# NIR_Schematic.net
KiCad netlist of a schematic drawn in EasyEDA
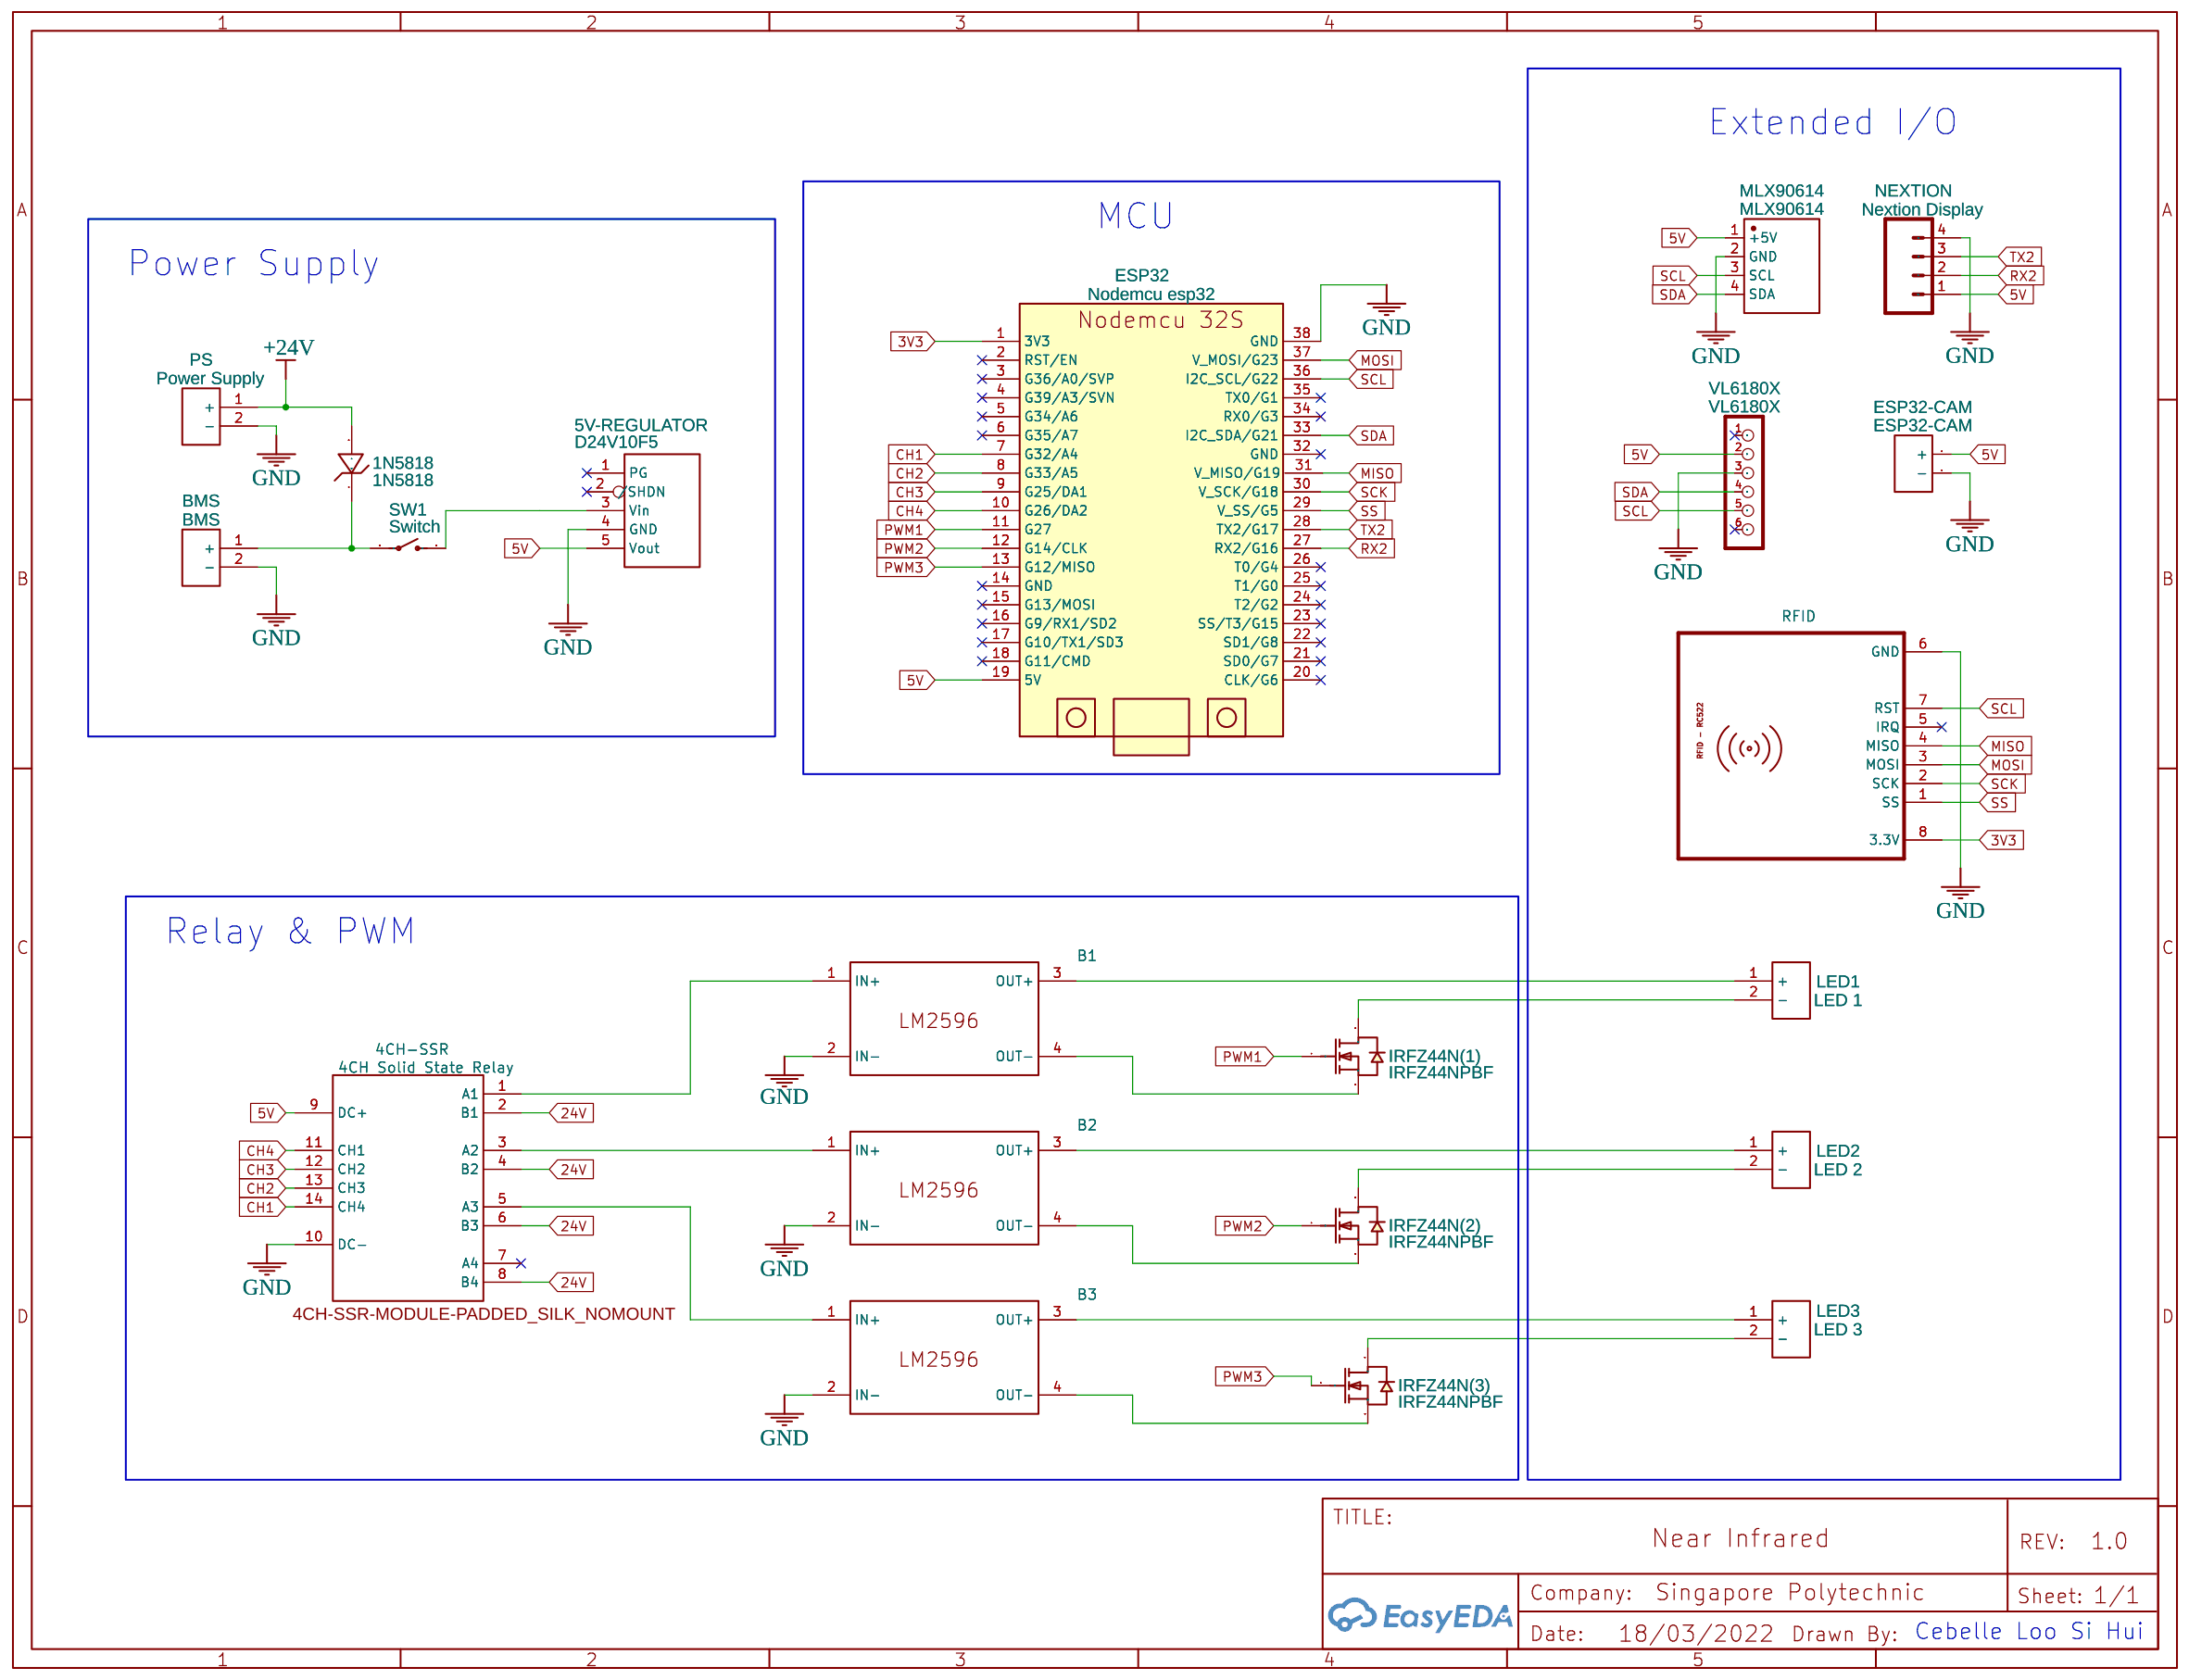
[diagram p0: schematic sheet]

(export (version "E")
  (design (tool "Eeschema 10.0.6"))
  (components
    (comp (ref "1N5818")
      (value "1N5818")
      (fields (field (name "BOM_Supplier Part") "C402217"))
      (libsource (lib "") (part "1N5818"))
    )
    (comp (ref "4CH-SSR") (value "4CH Solid State Relay") (libsource (lib "") (part "Unknown_210_-255")))
    (comp (ref "5V-REGULATOR") (value "D24V10F5") (libsource (lib "") (part "D24V10F5")))
    (comp (ref "B1") (value "NO") (libsource (lib "") (part "Unknown_495_-345")))
    (comp (ref "B2") (value "NO") (libsource (lib "") (part "Unknown_495_-255")))
    (comp (ref "B3") (value "NO") (libsource (lib "") (part "Unknown_495_-165")))
    (comp (ref "BMS")
      (value "BMS")
      (fields
        (field (name "BOM_Manufacturer Part") "WJ103-5.00-2P")
        (field (name "BOM_Supplier Part") "C8439")
      )
      (libsource (lib "") (part "WJ103-5.00-2P_1"))
    )
    (comp (ref "ESP32") (value "Nodemcu esp32") (libsource (lib "") (part "Nodemcu esp32")))
    (comp (ref "ESP32-CAM")
      (value "ESP32-CAM")
      (fields
        (field (name "BOM_Manufacturer Part") "2.54-1*2PFemale")
        (field (name "BOM_Supplier Part") "C49661")
      )
      (libsource (lib "") (part "Header-Female-2.54_1x2"))
    )
    (comp (ref "IRFZ44N(1)")
      (value "IRFZ44NPBF")
      (fields (field (name "BOM_Supplier Part") "C2586"))
      (libsource (lib "") (part "IRFZ44NPBF_1"))
    )
    (comp (ref "IRFZ44N(2)")
      (value "IRFZ44NPBF")
      (fields (field (name "BOM_Supplier Part") "C2586"))
      (libsource (lib "") (part "IRFZ44NPBF_2"))
    )
    (comp (ref "IRFZ44N(3)")
      (value "IRFZ44NPBF")
      (fields (field (name "BOM_Supplier Part") "C2586"))
      (libsource (lib "") (part "IRFZ44NPBF"))
    )
    (comp (ref "LED1")
      (value "LED 1")
      (fields
        (field (name "BOM_Manufacturer Part") "WJ103-5.00-2P")
        (field (name "BOM_Supplier Part") "C8439")
      )
      (libsource (lib "") (part "WJ103-5.00-2P_2"))
    )
    (comp (ref "LED2")
      (value "LED 2")
      (fields
        (field (name "BOM_Manufacturer Part") "WJ103-5.00-2P")
        (field (name "BOM_Supplier Part") "C8439")
      )
      (libsource (lib "") (part "WJ103-5.00-2P_2"))
    )
    (comp (ref "LED3")
      (value "LED 3")
      (fields
        (field (name "BOM_Manufacturer Part") "WJ103-5.00-2P")
        (field (name "BOM_Supplier Part") "C8439")
      )
      (libsource (lib "") (part "WJ103-5.00-2P_2"))
    )
    (comp (ref "MLX90614")
      (value "MLX90614")
      (fields
        (field (name "BOM_Manufacturer Part") "RE-H042TD-1190(LF)(SN)")
        (field (name "BOM_Supplier Part") "C265319")
      )
      (libsource (lib "") (part "RE-H042TD-1190(LF)(SN)"))
    )
    (comp (ref "NEXTION") (value "Nextion Display") (libsource (lib "") (part "M04POLAR")))
    (comp (ref "PS")
      (value "Power Supply")
      (fields
        (field (name "BOM_Manufacturer Part") "WJ103-5.00-2P")
        (field (name "BOM_Supplier Part") "C8439")
      )
      (libsource (lib "") (part "WJ103-5.00-2P"))
    )
    (comp (ref "RFID") (value "NO") (libsource (lib "") (part "Unknown_954_-490")))
    (comp (ref "SW1")
      (value "Switch")
      (fields (field (name "BOM_Manufacturer Part") "KCD1-11-1.5x1cm"))
      (libsource (lib "") (part "SWITCH-2P-SPST-Rocker-10x15mm"))
    )
    (comp (ref "VL6180X") (value "VL6180X") (libsource (lib "") (part "CON_HEADER_1X06-PTH")))
  )
  (nets
    (net (code "1") (name "+24V") (class "Default")
      (node (ref "1N5818") (pin "2") (pinfunction "A_2") (pintype "unspecified"))
      (node (ref "PS") (pin "1") (pinfunction "+_1") (pintype "unspecified"))
    )
    (net (code "2") (name "3V3") (class "Default")
      (node (ref "ESP32") (pin "1") (pinfunction "3V3_1") (pintype "passive"))
      (node (ref "RFID") (pin "8") (pinfunction "3.3V_8") (pintype "unspecified"))
    )
    (net (code "3") (name "5V") (class "Default")
      (node (ref "4CH-SSR") (pin "9") (pinfunction "DC+_9") (pintype "unspecified"))
      (node (ref "5V-REGULATOR") (pin "5") (pinfunction "Vout_5") (pintype "unspecified"))
      (node (ref "ESP32") (pin "19") (pinfunction "5V_19") (pintype "passive"))
      (node (ref "ESP32-CAM") (pin "2") (pinfunction "+_2") (pintype "input"))
      (node (ref "MLX90614") (pin "1") (pinfunction "+5V_1") (pintype "unspecified"))
      (node (ref "NEXTION") (pin "1") (pinfunction "GND_1") (pintype "unspecified"))
      (node (ref "VL6180X") (pin "2") (pinfunction "VIN_2") (pintype "unspecified"))
    )
    (net (code "4") (name "24V") (class "Default")
      (node (ref "4CH-SSR") (pin "2") (pinfunction "B1_2") (pintype "unspecified"))
      (node (ref "4CH-SSR") (pin "4") (pinfunction "B2_4") (pintype "unspecified"))
      (node (ref "4CH-SSR") (pin "6") (pinfunction "B3_6") (pintype "unspecified"))
      (node (ref "4CH-SSR") (pin "8") (pinfunction "B4_8") (pintype "unspecified"))
    )
    (net (code "5") (name "CH1") (class "Default")
      (node (ref "4CH-SSR") (pin "14") (pinfunction "CH4_14") (pintype "unspecified"))
      (node (ref "ESP32") (pin "7") (pinfunction "G32/A4_7") (pintype "bidirectional"))
    )
    (net (code "6") (name "CH2") (class "Default")
      (node (ref "4CH-SSR") (pin "13") (pinfunction "CH3_13") (pintype "unspecified"))
      (node (ref "ESP32") (pin "8") (pinfunction "G33/A5_8") (pintype "bidirectional"))
    )
    (net (code "7") (name "CH3") (class "Default")
      (node (ref "4CH-SSR") (pin "12") (pinfunction "CH2_12") (pintype "unspecified"))
      (node (ref "ESP32") (pin "9") (pinfunction "G25/DA1_9") (pintype "bidirectional"))
    )
    (net (code "8") (name "CH4") (class "Default")
      (node (ref "4CH-SSR") (pin "11") (pinfunction "CH1_11") (pintype "unspecified"))
      (node (ref "ESP32") (pin "10") (pinfunction "G26/DA2_10") (pintype "bidirectional"))
    )
    (net (code "9") (name "GND") (class "Default")
      (node (ref "4CH-SSR") (pin "10") (pinfunction "DC-_10") (pintype "unspecified"))
      (node (ref "5V-REGULATOR") (pin "4") (pinfunction "GND_4") (pintype "unspecified"))
      (node (ref "B1") (pin "2") (pinfunction "IN-_2") (pintype "unspecified"))
      (node (ref "B2") (pin "2") (pinfunction "IN-_2") (pintype "unspecified"))
      (node (ref "B3") (pin "2") (pinfunction "IN-_2") (pintype "unspecified"))
      (node (ref "BMS") (pin "2") (pinfunction "-_2") (pintype "unspecified"))
      (node (ref "ESP32") (pin "38") (pinfunction "GND_38") (pintype "passive"))
      (node (ref "ESP32-CAM") (pin "1") (pinfunction "-_1") (pintype "input"))
      (node (ref "MLX90614") (pin "2") (pinfunction "GND_2") (pintype "unspecified"))
      (node (ref "NEXTION") (pin "4") (pinfunction "+5V_4") (pintype "unspecified"))
      (node (ref "PS") (pin "2") (pinfunction "-_2") (pintype "unspecified"))
      (node (ref "RFID") (pin "6") (pinfunction "GND_6") (pintype "unspecified"))
      (node (ref "VL6180X") (pin "3") (pinfunction "GND_3") (pintype "unspecified"))
    )
    (net (code "10") (name "MISO") (class "Default")
      (node (ref "ESP32") (pin "31") (pinfunction "V_MISO/G19_31") (pintype "bidirectional"))
      (node (ref "RFID") (pin "4") (pinfunction "MISO_4") (pintype "unspecified"))
    )
    (net (code "11") (name "MOSI") (class "Default")
      (node (ref "ESP32") (pin "37") (pinfunction "V_MOSI/G23_37") (pintype "bidirectional"))
      (node (ref "RFID") (pin "3") (pinfunction "MOSI_3") (pintype "unspecified"))
    )
    (net (code "12") (name "Net-(1N5818-C)") (class "Default")
      (node (ref "1N5818") (pin "1") (pinfunction "C_1") (pintype "unspecified"))
      (node (ref "BMS") (pin "1") (pinfunction "+_1") (pintype "unspecified"))
      (node (ref "SW1") (pin "2") (pinfunction "P_2") (pintype "unspecified"))
    )
    (net (code "13") (name "Net-(4CH-SSR-A1)") (class "Default")
      (node (ref "4CH-SSR") (pin "1") (pinfunction "A1_1") (pintype "unspecified"))
      (node (ref "B1") (pin "1") (pinfunction "IN+_1") (pintype "unspecified"))
    )
    (net (code "14") (name "Net-(4CH-SSR-A2)") (class "Default")
      (node (ref "4CH-SSR") (pin "3") (pinfunction "A2_3") (pintype "unspecified"))
      (node (ref "B2") (pin "1") (pinfunction "IN+_1") (pintype "unspecified"))
    )
    (net (code "15") (name "Net-(4CH-SSR-A3)") (class "Default")
      (node (ref "4CH-SSR") (pin "5") (pinfunction "A3_5") (pintype "unspecified"))
      (node (ref "B3") (pin "1") (pinfunction "IN+_1") (pintype "unspecified"))
    )
    (net (code "16") (name "Net-(5V-REGULATOR-Vin)") (class "Default")
      (node (ref "5V-REGULATOR") (pin "3") (pinfunction "Vin_3") (pintype "unspecified"))
      (node (ref "SW1") (pin "1") (pinfunction "O_1") (pintype "unspecified"))
    )
    (net (code "17") (name "Net-(B1-OUT+)") (class "Default")
      (node (ref "B1") (pin "3") (pinfunction "OUT+_3") (pintype "unspecified"))
      (node (ref "LED1") (pin "1") (pinfunction "+_1") (pintype "unspecified"))
    )
    (net (code "18") (name "Net-(B1-OUT-)") (class "Default")
      (node (ref "B1") (pin "4") (pinfunction "OUT-_4") (pintype "unspecified"))
      (node (ref "IRFZ44N(1)") (pin "3") (pinfunction "S_3") (pintype "unspecified"))
    )
    (net (code "19") (name "Net-(B2-OUT+)") (class "Default")
      (node (ref "B2") (pin "3") (pinfunction "OUT+_3") (pintype "unspecified"))
      (node (ref "LED2") (pin "1") (pinfunction "+_1") (pintype "unspecified"))
    )
    (net (code "20") (name "Net-(B2-OUT-)") (class "Default")
      (node (ref "B2") (pin "4") (pinfunction "OUT-_4") (pintype "unspecified"))
      (node (ref "IRFZ44N(2)") (pin "3") (pinfunction "S_3") (pintype "unspecified"))
    )
    (net (code "21") (name "Net-(B3-OUT+)") (class "Default")
      (node (ref "B3") (pin "3") (pinfunction "OUT+_3") (pintype "unspecified"))
      (node (ref "LED3") (pin "1") (pinfunction "+_1") (pintype "unspecified"))
    )
    (net (code "22") (name "Net-(B3-OUT-)") (class "Default")
      (node (ref "B3") (pin "4") (pinfunction "OUT-_4") (pintype "unspecified"))
      (node (ref "IRFZ44N(3)") (pin "3") (pinfunction "S_3") (pintype "unspecified"))
    )
    (net (code "23") (name "Net-(IRFZ44N(1)-D)") (class "Default")
      (node (ref "IRFZ44N(1)") (pin "2") (pinfunction "D_2") (pintype "unspecified"))
      (node (ref "LED1") (pin "2") (pinfunction "-_2") (pintype "unspecified"))
    )
    (net (code "24") (name "Net-(IRFZ44N(2)-D)") (class "Default")
      (node (ref "IRFZ44N(2)") (pin "2") (pinfunction "D_2") (pintype "unspecified"))
      (node (ref "LED2") (pin "2") (pinfunction "-_2") (pintype "unspecified"))
    )
    (net (code "25") (name "Net-(IRFZ44N(3)-D)") (class "Default")
      (node (ref "IRFZ44N(3)") (pin "2") (pinfunction "D_2") (pintype "unspecified"))
      (node (ref "LED3") (pin "2") (pinfunction "-_2") (pintype "unspecified"))
    )
    (net (code "26") (name "PWM1") (class "Default")
      (node (ref "ESP32") (pin "11") (pinfunction "G27_11") (pintype "bidirectional"))
      (node (ref "IRFZ44N(1)") (pin "1") (pinfunction "G_1") (pintype "unspecified"))
    )
    (net (code "27") (name "PWM2") (class "Default")
      (node (ref "ESP32") (pin "12") (pinfunction "G14/CLK_12") (pintype "bidirectional"))
      (node (ref "IRFZ44N(2)") (pin "1") (pinfunction "G_1") (pintype "unspecified"))
    )
    (net (code "28") (name "PWM3") (class "Default")
      (node (ref "ESP32") (pin "13") (pinfunction "G12/MISO_13") (pintype "bidirectional"))
      (node (ref "IRFZ44N(3)") (pin "1") (pinfunction "G_1") (pintype "unspecified"))
    )
    (net (code "29") (name "RX2") (class "Default")
      (node (ref "ESP32") (pin "27") (pinfunction "RX2/G16_27") (pintype "bidirectional"))
      (node (ref "NEXTION") (pin "2") (pinfunction "RX_2") (pintype "unspecified"))
    )
    (net (code "30") (name "SCK") (class "Default")
      (node (ref "ESP32") (pin "30") (pinfunction "V_SCK/G18_30") (pintype "bidirectional"))
      (node (ref "RFID") (pin "2") (pinfunction "SCK_2") (pintype "unspecified"))
    )
    (net (code "31") (name "SCL") (class "Default")
      (node (ref "ESP32") (pin "36") (pinfunction "I2C_SCL/G22_36") (pintype "bidirectional"))
      (node (ref "MLX90614") (pin "3") (pinfunction "SCL_3") (pintype "unspecified"))
      (node (ref "RFID") (pin "7") (pinfunction "RST_7") (pintype "unspecified"))
      (node (ref "VL6180X") (pin "5") (pinfunction "SCL_5") (pintype "unspecified"))
    )
    (net (code "32") (name "SDA") (class "Default")
      (node (ref "ESP32") (pin "33") (pinfunction "I2C_SDA/G21_33") (pintype "bidirectional"))
      (node (ref "MLX90614") (pin "4") (pinfunction "SDA_4") (pintype "unspecified"))
      (node (ref "VL6180X") (pin "4") (pinfunction "SDA_4") (pintype "unspecified"))
    )
    (net (code "33") (name "SS") (class "Default")
      (node (ref "ESP32") (pin "29") (pinfunction "V_SS/G5_29") (pintype "bidirectional"))
      (node (ref "RFID") (pin "1") (pinfunction "SS_1") (pintype "unspecified"))
    )
    (net (code "34") (name "TX2") (class "Default")
      (node (ref "ESP32") (pin "28") (pinfunction "TX2/G17_28") (pintype "bidirectional"))
      (node (ref "NEXTION") (pin "3") (pinfunction "TX_3") (pintype "unspecified"))
    )
    (net (code "35") (name "unconnected-(4CH-SSR-A4-Pad7)") (class "Default")
      (node (ref "4CH-SSR") (pin "7") (pinfunction "A4_7") (pintype "unspecified+no_connect"))
    )
    (net (code "36") (name "unconnected-(5V-REGULATOR-PG-Pad1)") (class "Default")
      (node (ref "5V-REGULATOR") (pin "1") (pinfunction "PG_1") (pintype "unspecified+no_connect"))
    )
    (net (code "37") (name "unconnected-(5V-REGULATOR-{slash}SHDN-Pad2)") (class "Default")
      (node (ref "5V-REGULATOR") (pin "2") (pinfunction "/SHDN_2") (pintype "unspecified+no_connect"))
    )
    (net (code "38") (name "unconnected-(ESP32-CLK{slash}G6-Pad20)") (class "Default")
      (node (ref "ESP32") (pin "20") (pinfunction "CLK/G6_20") (pintype "bidirectional+no_connect"))
    )
    (net (code "39") (name "unconnected-(ESP32-G9{slash}RX1{slash}SD2-Pad16)") (class "Default")
      (node (ref "ESP32") (pin "16") (pinfunction "G9/RX1/SD2_16") (pintype "bidirectional+no_connect"))
    )
    (net (code "40") (name "unconnected-(ESP32-G10{slash}TX1{slash}SD3-Pad17)") (class "Default")
      (node (ref "ESP32") (pin "17") (pinfunction "G10/TX1/SD3_17") (pintype "bidirectional+no_connect"))
    )
    (net (code "41") (name "unconnected-(ESP32-G11{slash}CMD-Pad18)") (class "Default")
      (node (ref "ESP32") (pin "18") (pinfunction "G11/CMD_18") (pintype "bidirectional+no_connect"))
    )
    (net (code "42") (name "unconnected-(ESP32-G13{slash}MOSI-Pad15)") (class "Default")
      (node (ref "ESP32") (pin "15") (pinfunction "G13/MOSI_15") (pintype "bidirectional+no_connect"))
    )
    (net (code "43") (name "unconnected-(ESP32-G34{slash}A6-Pad5)") (class "Default")
      (node (ref "ESP32") (pin "5") (pinfunction "G34/A6_5") (pintype "bidirectional+no_connect"))
    )
    (net (code "44") (name "unconnected-(ESP32-G35{slash}A7-Pad6)") (class "Default")
      (node (ref "ESP32") (pin "6") (pinfunction "G35/A7_6") (pintype "bidirectional+no_connect"))
    )
    (net (code "45") (name "unconnected-(ESP32-G36{slash}A0{slash}SVP-Pad3)") (class "Default")
      (node (ref "ESP32") (pin "3") (pinfunction "G36/A0/SVP_3") (pintype "bidirectional+no_connect"))
    )
    (net (code "46") (name "unconnected-(ESP32-G39{slash}A3{slash}SVN-Pad4)") (class "Default")
      (node (ref "ESP32") (pin "4") (pinfunction "G39/A3/SVN_4") (pintype "bidirectional+no_connect"))
    )
    (net (code "47") (name "unconnected-(ESP32-GND-Pad14)") (class "Default")
      (node (ref "ESP32") (pin "14") (pinfunction "GND_14") (pintype "passive+no_connect"))
    )
    (net (code "48") (name "unconnected-(ESP32-GND-Pad32)") (class "Default")
      (node (ref "ESP32") (pin "32") (pinfunction "GND_32") (pintype "passive+no_connect"))
    )
    (net (code "49") (name "unconnected-(ESP32-RST{slash}EN-Pad2)") (class "Default")
      (node (ref "ESP32") (pin "2") (pinfunction "RST/EN_2") (pintype "bidirectional+no_connect"))
    )
    (net (code "50") (name "unconnected-(ESP32-RX0{slash}G3-Pad34)") (class "Default")
      (node (ref "ESP32") (pin "34") (pinfunction "RX0/G3_34") (pintype "bidirectional+no_connect"))
    )
    (net (code "51") (name "unconnected-(ESP32-SD0{slash}G7-Pad21)") (class "Default")
      (node (ref "ESP32") (pin "21") (pinfunction "SD0/G7_21") (pintype "bidirectional+no_connect"))
    )
    (net (code "52") (name "unconnected-(ESP32-SD1{slash}G8-Pad22)") (class "Default")
      (node (ref "ESP32") (pin "22") (pinfunction "SD1/G8_22") (pintype "bidirectional+no_connect"))
    )
    (net (code "53") (name "unconnected-(ESP32-SS{slash}T3{slash}G15-Pad23)") (class "Default")
      (node (ref "ESP32") (pin "23") (pinfunction "SS/T3/G15_23") (pintype "bidirectional+no_connect"))
    )
    (net (code "54") (name "unconnected-(ESP32-T0{slash}G4-Pad26)") (class "Default")
      (node (ref "ESP32") (pin "26") (pinfunction "T0/G4_26") (pintype "bidirectional+no_connect"))
    )
    (net (code "55") (name "unconnected-(ESP32-T1{slash}G0-Pad25)") (class "Default")
      (node (ref "ESP32") (pin "25") (pinfunction "T1/G0_25") (pintype "bidirectional+no_connect"))
    )
    (net (code "56") (name "unconnected-(ESP32-T2{slash}G2-Pad24)") (class "Default")
      (node (ref "ESP32") (pin "24") (pinfunction "T2/G2_24") (pintype "bidirectional+no_connect"))
    )
    (net (code "57") (name "unconnected-(ESP32-TX0{slash}G1-Pad35)") (class "Default")
      (node (ref "ESP32") (pin "35") (pinfunction "TX0/G1_35") (pintype "bidirectional+no_connect"))
    )
    (net (code "58") (name "unconnected-(RFID-IRQ-Pad5)") (class "Default")
      (node (ref "RFID") (pin "5") (pinfunction "IRQ_5") (pintype "unspecified+no_connect"))
    )
    (net (code "59") (name "unconnected-(VL6180X-IO1-Pad6)") (class "Default")
      (node (ref "VL6180X") (pin "6") (pinfunction "IO1_6") (pintype "unspecified+no_connect"))
    )
    (net (code "60") (name "unconnected-(VL6180X-VDD-Pad1)") (class "Default")
      (node (ref "VL6180X") (pin "1") (pinfunction "VDD_1") (pintype "unspecified+no_connect"))
    )
  )
)
